# Converters.net
KiCad netlist of a schematic drawn in Altium Designer
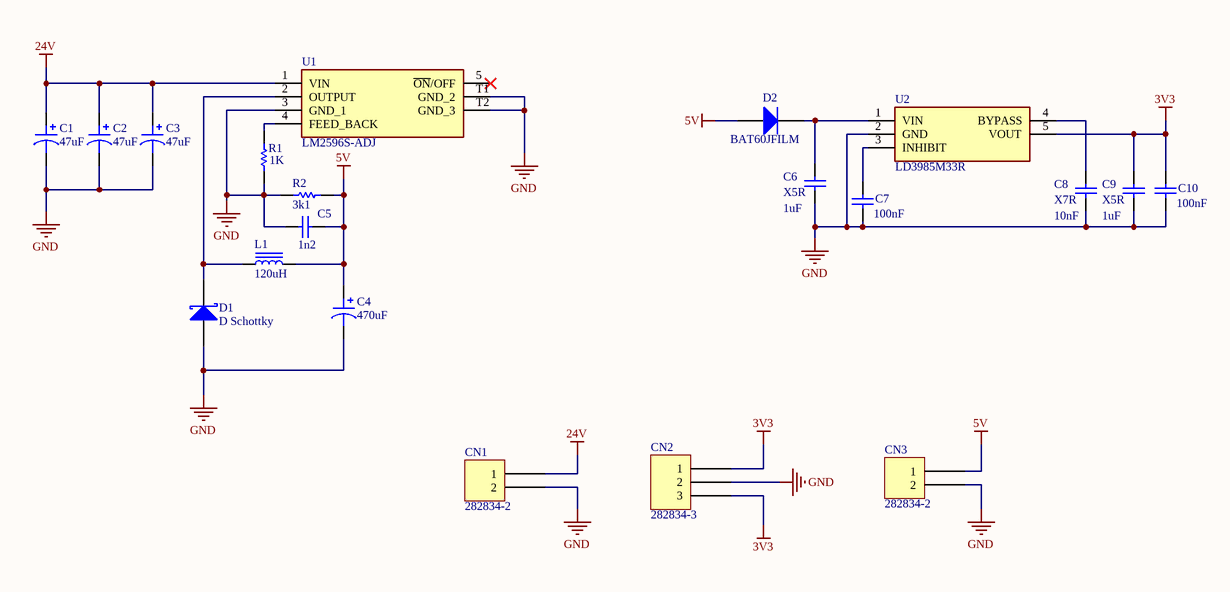
[diagram p0: Converters.SchDoc]

(export (version "E")
  (design (tool "Eeschema 10.0.6"))
  (components
    (comp (ref "C1")
      (value "47uF")
      (footprint "CAP ALSMD 6.6MM H6.1MM")
      (description "CAP ALUM 68UF 20% 16V SMD")
      (fields (field (name "PART NUMBER") "UUD1C680MCL1GS") (field (name "MANUFACTURER") "Nichicon"))
      (libsource (lib "Celestial Altium Library - altium_library") (part "Polarised Capacitor"))
    )
    (comp (ref "C2")
      (value "47uF")
      (footprint "CAP ALSMD 6.6MM H6.1MM")
      (description "CAP ALUM 68UF 20% 16V SMD")
      (fields (field (name "PART NUMBER") "UUD1C680MCL1GS") (field (name "MANUFACTURER") "Nichicon"))
      (libsource (lib "Celestial Altium Library - altium_library") (part "Polarised Capacitor"))
    )
    (comp (ref "C3")
      (value "47uF")
      (footprint "CAP ALSMD 6.6MM H6.1MM")
      (description "CAP ALUM 68UF 20% 16V SMD")
      (fields (field (name "PART NUMBER") "UUD1C680MCL1GS") (field (name "MANUFACTURER") "Nichicon"))
      (libsource (lib "Celestial Altium Library - altium_library") (part "Polarised Capacitor"))
    )
    (comp (ref "C4")
      (value "470uF")
      (footprint "CAP ALSMD 6.6MM H6.1MM")
      (description "CAP ALUM 68UF 20% 16V SMD")
      (fields (field (name "PART NUMBER") "UUD1C680MCL1GS") (field (name "MANUFACTURER") "Nichicon"))
      (libsource (lib "Celestial Altium Library - altium_library") (part "Polarised Capacitor"))
    )
    (comp (ref "C5")
      (value "1n2")
      (footprint "1608[0603]")
      (description "Capacitor")
      (fields (field (name "Comment") "X5R") (field (name "PUBLISHER") "Altium Limited"))
      (libsource (lib "Miscellaneous Devices") (part "Cap"))
    )
    (comp (ref "C6")
      (value "X5R")
      (footprint "1608[0603]")
      (description "Capacitor")
      (fields (field (name "ALTIUM_VALUE") "1uF") (field (name "PUBLISHER") "Altium Limited"))
      (libsource (lib "Miscellaneous Devices") (part "Cap"))
    )
    (comp (ref "C7")
      (value "100nF")
      (footprint "1608[0603]")
      (description "Capacitor")
      (fields (field (name "Comment") "X5R") (field (name "PUBLISHER") "Altium Limited"))
      (libsource (lib "Miscellaneous Devices") (part "Cap"))
    )
    (comp (ref "C8")
      (value "X7R")
      (footprint "1608[0603]")
      (description "Capacitor")
      (fields (field (name "ALTIUM_VALUE") "10nF") (field (name "PUBLISHER") "Altium Limited"))
      (libsource (lib "Miscellaneous Devices") (part "Cap"))
    )
    (comp (ref "C9")
      (value "X5R")
      (footprint "1608[0603]")
      (description "Capacitor")
      (fields (field (name "ALTIUM_VALUE") "1uF") (field (name "PUBLISHER") "Altium Limited"))
      (libsource (lib "Miscellaneous Devices") (part "Cap"))
    )
    (comp (ref "C10")
      (value "100nF")
      (footprint "1608[0603]")
      (description "Capacitor")
      (fields (field (name "Comment") "X5R") (field (name "PUBLISHER") "Altium Limited"))
      (libsource (lib "Miscellaneous Devices") (part "Cap"))
    )
    (comp (ref "CN1")
      (value "282834-2")
      (footprint "TE 282834-2")
      (description "TERM BLK 2P SIDE ENT 2.54MM PCB")
      (fields (field (name "MANUFACTURER") "TE Connectivity AMP Connectors") (field (name "VOLTAGE") "150V"))
      (libsource (lib "Celestial Altium Library - altium_library") (part "2 Pin"))
    )
    (comp (ref "CN2")
      (value "282834-3")
      (footprint "TE 282834-3")
      (description "TERM BLK 3P SIDE ENT 2.54MM PCB")
      (fields (field (name "MANUFACTURER") "TE Connectivity AMP Connectors") (field (name "VOLTAGE") "150V"))
      (libsource (lib "Celestial Altium Library - altium_library") (part "3 Pin"))
    )
    (comp (ref "CN3")
      (value "282834-2")
      (footprint "TE 282834-2")
      (description "TERM BLK 2P SIDE ENT 2.54MM PCB")
      (fields (field (name "MANUFACTURER") "TE Connectivity AMP Connectors") (field (name "VOLTAGE") "150V"))
      (libsource (lib "Celestial Altium Library - altium_library") (part "2 Pin"))
    )
    (comp (ref "D1")
      (value "D Schottky")
      (footprint "C0805")
      (description "Schottky Diode")
      (fields (field (name "PUBLISHER") "Altium Limited"))
      (libsource (lib "Miscellaneous Devices") (part "D Schottky"))
    )
    (comp (ref "D2")
      (value "BAT60JFILM")
      (footprint "C0805")
      (description "Default Diode")
      (fields (field (name "PUBLISHER") "Altium Limited"))
      (libsource (lib "Miscellaneous Devices") (part "Diode"))
    )
    (comp (ref "L1")
      (value "120uH")
      (footprint "IND 0806_2016")
      (description "FIXED IND 10UH 470MA 1.119OHM SM")
      (fields
        (field (name "PART NUMBER") "SDED20161T-100MS")
        (field (name "MANUFACTURER") "Delta Electronics/Cyntec")
      )
      (libsource (lib "Celestial Altium Library - altium_library") (part "Inductor"))
    )
    (comp (ref "R1")
      (value "1K")
      (footprint "1608[0603]")
      (description "Resistor")
      (fields (field (name "Comment") "Res1") (field (name "PUBLISHER") "Altium Limited"))
      (libsource (lib "Miscellaneous Devices") (part "Res1"))
    )
    (comp (ref "R2")
      (value "3k1")
      (footprint "1608[0603]")
      (description "Resistor")
      (fields (field (name "Comment") "Res1") (field (name "PUBLISHER") "Altium Limited"))
      (libsource (lib "Miscellaneous Devices") (part "Res1"))
    )
    (comp (ref "U1")
      (value "LM2596S-ADJ")
      (footprint "SamacSys:LM2596SXADJ")
      (description "Integrated Circuit")
      (fields (field (name "MOUSER PART NUMBER") "926-LM2596S-ADJ"))
      (libsource (lib "SamacSys") (part "LM2596S-ADJ"))
    )
    (comp (ref "U2")
      (value "LD3985M33R")
      (footprint "SamacSys:SOT95P280X145-5N")
      (description "Integrated Circuit")
      (fields (field (name "MOUSER PART NUMBER") "511-LD3985M33R"))
      (libsource (lib "*") (part "LD3985M33R"))
    )
  )
  (nets
    (net (code "1") (name "3V3") (class "Default")
      (node (ref "C10") (pin "1") (pinfunction "1_1") (pintype "passive"))
      (node (ref "C9") (pin "2") (pinfunction "2_2") (pintype "passive"))
      (node (ref "CN2") (pin "1") (pinfunction "1_1") (pintype "passive"))
      (node (ref "CN2") (pin "3") (pinfunction "3_3") (pintype "passive"))
      (node (ref "U2") (pin "5") (pinfunction "VOUT_5") (pintype "passive"))
    )
    (net (code "2") (name "5V") (class "Default")
      (node (ref "C4") (pin "1") (pinfunction "1_1") (pintype "passive"))
      (node (ref "C5") (pin "2") (pinfunction "2_2") (pintype "passive"))
      (node (ref "CN3") (pin "1") (pinfunction "1_1") (pintype "passive"))
      (node (ref "D2") (pin "1") (pinfunction "A_1") (pintype "passive"))
      (node (ref "L1") (pin "2") (pinfunction "2_2") (pintype "passive"))
      (node (ref "R2") (pin "1") (pinfunction "1_1") (pintype "passive"))
    )
    (net (code "3") (name "24V") (class "Default")
      (node (ref "C1") (pin "1") (pinfunction "1_1") (pintype "passive"))
      (node (ref "C2") (pin "1") (pinfunction "1_1") (pintype "passive"))
      (node (ref "C3") (pin "1") (pinfunction "1_1") (pintype "passive"))
      (node (ref "CN1") (pin "1") (pinfunction "1_1") (pintype "passive"))
      (node (ref "U1") (pin "1") (pinfunction "VIN_1") (pintype "passive"))
    )
    (net (code "4") (name "GND") (class "Default")
      (node (ref "C1") (pin "2") (pinfunction "2_2") (pintype "passive"))
      (node (ref "C10") (pin "2") (pinfunction "2_2") (pintype "passive"))
      (node (ref "C2") (pin "2") (pinfunction "2_2") (pintype "passive"))
      (node (ref "C3") (pin "2") (pinfunction "2_2") (pintype "passive"))
      (node (ref "C4") (pin "2") (pinfunction "2_2") (pintype "passive"))
      (node (ref "C5") (pin "1") (pinfunction "1_1") (pintype "passive"))
      (node (ref "C6") (pin "1") (pinfunction "1_1") (pintype "passive"))
      (node (ref "C7") (pin "2") (pinfunction "2_2") (pintype "passive"))
      (node (ref "C8") (pin "1") (pinfunction "1_1") (pintype "passive"))
      (node (ref "C9") (pin "1") (pinfunction "1_1") (pintype "passive"))
      (node (ref "CN1") (pin "2") (pinfunction "2_2") (pintype "passive"))
      (node (ref "CN2") (pin "2") (pinfunction "2_2") (pintype "passive"))
      (node (ref "CN3") (pin "2") (pinfunction "2_2") (pintype "passive"))
      (node (ref "D1") (pin "1") (pinfunction "A_1") (pintype "passive"))
      (node (ref "R1") (pin "1") (pinfunction "1_1") (pintype "passive"))
      (node (ref "R2") (pin "2") (pinfunction "2_2") (pintype "passive"))
      (node (ref "U1") (pin "3") (pinfunction "GND_1_3") (pintype "passive"))
      (node (ref "U1") (pin "T1") (pinfunction "GND_2_T1") (pintype "passive"))
      (node (ref "U1") (pin "T2") (pinfunction "GND_3_T2") (pintype "passive"))
      (node (ref "U2") (pin "2") (pinfunction "GND_2") (pintype "passive"))
    )
    (net (code "5") (name "Net-(D1-K)") (class "Default")
      (node (ref "D1") (pin "2") (pinfunction "K_2") (pintype "passive"))
      (node (ref "L1") (pin "1") (pinfunction "1_1") (pintype "passive"))
      (node (ref "U1") (pin "2") (pinfunction "OUTPUT_2") (pintype "passive"))
    )
    (net (code "6") (name "Net-(D2-K)") (class "Default")
      (node (ref "C6") (pin "2") (pinfunction "2_2") (pintype "passive"))
      (node (ref "D2") (pin "2") (pinfunction "K_2") (pintype "passive"))
      (node (ref "U2") (pin "1") (pinfunction "VIN_1") (pintype "passive"))
    )
    (net (code "7") (name "Net-(U1-FEED_BACK)") (class "Default")
      (node (ref "R1") (pin "2") (pinfunction "2_2") (pintype "passive"))
      (node (ref "U1") (pin "4") (pinfunction "FEED_BACK_4") (pintype "passive"))
    )
    (net (code "8") (name "Net-(U2-BYPASS)") (class "Default")
      (node (ref "C8") (pin "2") (pinfunction "2_2") (pintype "passive"))
      (node (ref "U2") (pin "4") (pinfunction "BYPASS_4") (pintype "passive"))
    )
    (net (code "9") (name "Net-(U2-INHIBIT)") (class "Default")
      (node (ref "C7") (pin "1") (pinfunction "1_1") (pintype "passive"))
      (node (ref "U2") (pin "3") (pinfunction "INHIBIT_3") (pintype "passive"))
    )
    (net (code "10") (name "unconnected-(U1-~{ON}{slash}OFF-Pad5)") (class "Default")
      (node (ref "U1") (pin "5") (pinfunction "~{ON}/OFF_5") (pintype "passive+no_connect"))
    )
  )
)
